# glitchprog1b-update.net
KiCad netlist of a schematic drawn in EAGLE
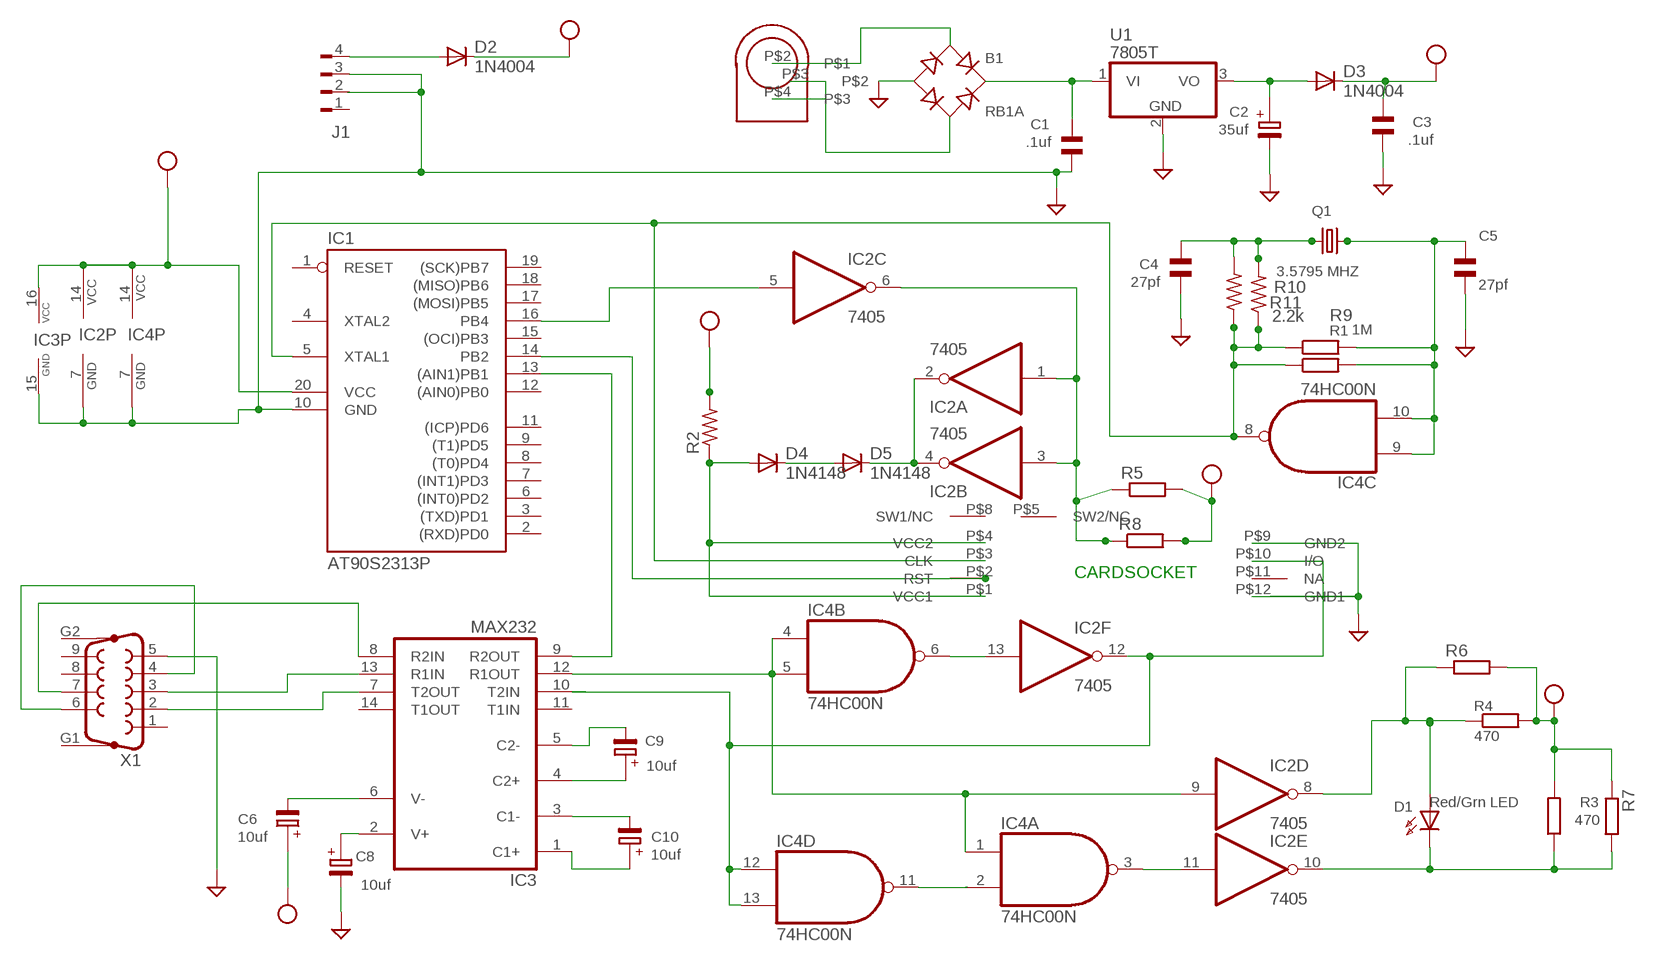
[diagram p0: schematic, sheet 1]

(export (version "E")
  (design (tool "Eeschema 10.0.6"))
  (components
    (comp (ref "B1")
      (value "RB1A")
      (footprint "eagle-import:RB1A")
      (libsource (lib "eagle-import") (part "RB1A"))
    )
    (comp (ref "C1")
      (value ".1uf")
      (footprint "eagle-import:C5B3")
      (libsource (lib "eagle-import") (part "C2,5"))
    )
    (comp (ref "C2")
      (value "35uf")
      (footprint "eagle-import:E2,0-5")
      (libsource (lib "eagle-import") (part "E2,0-5"))
    )
    (comp (ref "C3")
      (value ".1uf")
      (footprint "eagle-import:C5B3")
      (libsource (lib "eagle-import") (part "C2,5"))
    )
    (comp (ref "C4")
      (value "27pf")
      (footprint "eagle-import:C5B3")
      (libsource (lib "eagle-import") (part "C2,5"))
    )
    (comp (ref "C5")
      (value "27pf")
      (footprint "eagle-import:C5B3")
      (libsource (lib "eagle-import") (part "C2,5"))
    )
    (comp (ref "C6")
      (value "10uf")
      (footprint "eagle-import:E2,0-5")
      (libsource (lib "eagle-import") (part "E2,0-5"))
    )
    (comp (ref "C8")
      (value "10uf")
      (footprint "eagle-import:E2,0-5")
      (libsource (lib "eagle-import") (part "E2,0-5"))
    )
    (comp (ref "C9")
      (value "10uf")
      (footprint "eagle-import:E2,0-5")
      (libsource (lib "eagle-import") (part "E2,0-5"))
    )
    (comp (ref "C10")
      (value "10uf")
      (footprint "eagle-import:E2,0-5")
      (libsource (lib "eagle-import") (part "E2,0-5"))
    )
    (comp (ref "CDR1")
      (value "CHEAPREADR")
      (footprint "eagle-import:CHEAPREA")
      (libsource (lib "eagle-import") (part "CHEAPREADR"))
    )
    (comp (ref "D1")
      (value "Red/Grn LED")
      (footprint "eagle-import:LED2")
      (libsource (lib "eagle-import") (part "LED2"))
    )
    (comp (ref "D2")
      (value "1N4004")
      (footprint "eagle-import:DO41-10")
      (libsource (lib "eagle-import") (part "1N4004"))
    )
    (comp (ref "D3")
      (value "1N4004")
      (footprint "eagle-import:DO41-10")
      (libsource (lib "eagle-import") (part "1N4004"))
    )
    (comp (ref "D4")
      (value "1N4148")
      (footprint "eagle-import:DO35-10")
      (libsource (lib "eagle-import") (part "1N4148"))
    )
    (comp (ref "D5")
      (value "1N4148")
      (footprint "eagle-import:DO35-10")
      (libsource (lib "eagle-import") (part "1N4148"))
    )
    (comp (ref "IC1")
      (value "AT90S2313P")
      (footprint "eagle-import:DIL20")
      (libsource (lib "eagle-import") (part "AT90S2313P"))
    )
    (comp (ref "IC2")
      (value "7405")
      (footprint "eagle-import:DIL14")
      (libsource (lib "eagle-import") (part "7405"))
    )
    (comp (ref "IC3")
      (value "MAX232")
      (footprint "eagle-import:DIL16")
      (libsource (lib "eagle-import") (part "MAX232"))
    )
    (comp (ref "IC4")
      (value "74HC00N")
      (footprint "eagle-import:DIL14")
      (libsource (lib "eagle-import") (part "7400NALS"))
    )
    (comp (ref "J1")
      (value "FLOPPY-4")
      (footprint "eagle-import:FLOPPY-4")
      (libsource (lib "eagle-import") (part "FLOPPY-4"))
    )
    (comp (ref "Q1")
      (value "3.5795 MHZ")
      (footprint "eagle-import:HC49U-V")
      (libsource (lib "eagle-import") (part "HC49U-H"))
    )
    (comp (ref "R1")
      (value "1M")
      (footprint "eagle-import:1210")
      (libsource (lib "eagle-import") (part "0204V"))
    )
    (comp (ref "R2")
      (value "R-US_0207/10")
      (footprint "eagle-import:0207_10")
      (libsource (lib "eagle-import") (part "R-US_0207/10"))
    )
    (comp (ref "R3")
      (value "470")
      (footprint "eagle-import:1210")
      (libsource (lib "eagle-import") (part "0204V"))
    )
    (comp (ref "R4")
      (value "470")
      (footprint "eagle-import:1210@2")
      (libsource (lib "eagle-import") (part "0204/5"))
    )
    (comp (ref "R5")
      (value "R-EU_R2010")
      (footprint "eagle-import:R2010")
      (libsource (lib "eagle-import") (part "R-EU_R2010"))
    )
    (comp (ref "R6")
      (value "R-EU_0204/7")
      (footprint "eagle-import:0204_7")
      (libsource (lib "eagle-import") (part "R-EU_0204/7"))
    )
    (comp (ref "R7")
      (value "R-EU_0204/7")
      (footprint "eagle-import:0204_7")
      (libsource (lib "eagle-import") (part "R-EU_0204/7"))
    )
    (comp (ref "R8")
      (value "R-EU_0204/7")
      (footprint "eagle-import:0204_7")
      (libsource (lib "eagle-import") (part "R-EU_0204/7"))
    )
    (comp (ref "R9")
      (value "R-EU_0204/7")
      (footprint "eagle-import:0204_7")
      (libsource (lib "eagle-import") (part "R-EU_0204/7"))
    )
    (comp (ref "R10")
      (value "R-US_0204/7")
      (footprint "eagle-import:0204_7")
      (libsource (lib "eagle-import") (part "R-US_0204/7"))
    )
    (comp (ref "R11")
      (value "2.2k")
      (footprint "eagle-import:M1206")
      (libsource (lib "eagle-import") (part "R-US_M1206"))
    )
    (comp (ref "U$7")
      (value "POWER1")
      (footprint "eagle-import:POWER1")
      (libsource (lib "eagle-import") (part "POWER1"))
    )
    (comp (ref "U1")
      (value "7805T")
      (footprint "eagle-import:TO220H")
      (libsource (lib "eagle-import") (part "78XXT"))
    )
    (comp (ref "X1")
      (value "F09HP")
      (footprint "eagle-import:F09HP")
      (libsource (lib "eagle-import") (part "F09HP"))
    )
  )
  (nets
    (net (code "1") (name "GND") (class "Default")
      (node (ref "B1") (pin "-") (pinfunction "-_-") (pintype "passive"))
      (node (ref "C1") (pin "1") (pinfunction "1_1") (pintype "passive"))
      (node (ref "C2") (pin "-") (pinfunction "-_-") (pintype "passive"))
      (node (ref "C3") (pin "1") (pinfunction "1_1") (pintype "passive"))
      (node (ref "C4") (pin "1") (pinfunction "1_1") (pintype "passive"))
      (node (ref "C5") (pin "1") (pinfunction "1_1") (pintype "passive"))
      (node (ref "C8") (pin "-") (pinfunction "-_-") (pintype "passive"))
      (node (ref "CDR1") (pin "P$12") (pinfunction "GND1_P$12") (pintype "power_in"))
      (node (ref "CDR1") (pin "P$9") (pinfunction "GND2_P$9") (pintype "power_in"))
      (node (ref "IC1") (pin "10") (pinfunction "GND_10") (pintype "power_in"))
      (node (ref "IC2") (pin "7") (pinfunction "GND_7") (pintype "power_in"))
      (node (ref "IC3") (pin "15") (pinfunction "GND_15") (pintype "power_in"))
      (node (ref "IC4") (pin "7") (pinfunction "GND_7") (pintype "power_in"))
      (node (ref "J1") (pin "3") (pinfunction "3_3") (pintype "passive"))
      (node (ref "U1") (pin "2") (pinfunction "GND_2") (pintype "passive"))
      (node (ref "X1") (pin "5") (pinfunction "5_5") (pintype "passive"))
    )
    (net (code "2") (name "Net-(C4-Pad2)") (class "Default")
      (node (ref "C4") (pin "2") (pinfunction "2_2") (pintype "passive"))
      (node (ref "Q1") (pin "1") (pinfunction "1_1") (pintype "passive"))
      (node (ref "R10") (pin "2") (pinfunction "2_2") (pintype "passive"))
      (node (ref "R11") (pin "2") (pinfunction "2_2") (pintype "passive"))
    )
    (net (code "3") (name "Net-(CDR1-CLK)") (class "Default")
      (node (ref "CDR1") (pin "P$3") (pinfunction "CLK_P$3") (pintype "input"))
      (node (ref "IC1") (pin "5") (pinfunction "XTAL1_5") (pintype "bidirectional"))
      (node (ref "IC4") (pin "8") (pinfunction "O_8") (pintype "output"))
      (node (ref "R1") (pin "1") (pinfunction "1_1") (pintype "passive"))
      (node (ref "R10") (pin "1") (pinfunction "1_1") (pintype "passive"))
      (node (ref "R11") (pin "1") (pinfunction "1_1") (pintype "passive"))
      (node (ref "R9") (pin "1") (pinfunction "1_1") (pintype "passive"))
    )
    (net (code "4") (name "Net-(CDR1-I{slash}O)") (class "Default")
      (node (ref "CDR1") (pin "P$10") (pinfunction "I/O_P$10") (pintype "bidirectional"))
      (node (ref "IC2") (pin "12") (pinfunction "O_12") (pintype "open_collector"))
      (node (ref "IC3") (pin "10") (pinfunction "T2IN_10") (pintype "input"))
      (node (ref "IC4") (pin "12") (pinfunction "I0_12") (pintype "input"))
      (node (ref "IC4") (pin "13") (pinfunction "I1_13") (pintype "input"))
    )
    (net (code "5") (name "Net-(CDR1-RST)") (class "Default")
      (node (ref "CDR1") (pin "P$2") (pinfunction "RST_P$2") (pintype "input"))
      (node (ref "IC1") (pin "14") (pinfunction "PB2_14") (pintype "bidirectional"))
    )
    (net (code "6") (name "Net-(CDR1-VCC1)") (class "Default")
      (node (ref "CDR1") (pin "P$1") (pinfunction "VCC1_P$1") (pintype "power_in"))
      (node (ref "CDR1") (pin "P$4") (pinfunction "VCC2_P$4") (pintype "power_in"))
      (node (ref "D4") (pin "A") (pinfunction "A_A") (pintype "passive"))
      (node (ref "R2") (pin "1") (pinfunction "1_1") (pintype "passive"))
    )
    (net (code "7") (name "Net-(D2-PadA)") (class "Default")
      (node (ref "D2") (pin "A") (pinfunction "A_A") (pintype "passive"))
      (node (ref "J1") (pin "4") (pinfunction "4_4") (pintype "passive"))
    )
    (net (code "8") (name "Net-(D4-C)") (class "Default")
      (node (ref "D4") (pin "K") (pinfunction "C_K") (pintype "passive"))
      (node (ref "D5") (pin "A") (pinfunction "A_A") (pintype "passive"))
    )
    (net (code "9") (name "Net-(D5-C)") (class "Default")
      (node (ref "D5") (pin "K") (pinfunction "C_K") (pintype "passive"))
      (node (ref "IC2") (pin "2") (pinfunction "O_2") (pintype "open_collector"))
      (node (ref "IC2") (pin "4") (pinfunction "O_4") (pintype "open_collector"))
    )
    (net (code "10") (name "Net-(IC1-(AIN1)PB1)") (class "Default")
      (node (ref "IC1") (pin "13") (pinfunction "(AIN1)PB1_13") (pintype "bidirectional"))
      (node (ref "IC3") (pin "9") (pinfunction "R2OUT_9") (pintype "output"))
    )
    (net (code "11") (name "Net-(IC1-PB4)") (class "Default")
      (node (ref "IC1") (pin "16") (pinfunction "PB4_16") (pintype "bidirectional"))
      (node (ref "IC2") (pin "5") (pinfunction "I_5") (pintype "input"))
    )
    (net (code "12") (name "Net-(IC2A-I)") (class "Default")
      (node (ref "IC2") (pin "1") (pinfunction "I_1") (pintype "input"))
      (node (ref "IC2") (pin "3") (pinfunction "I_3") (pintype "input"))
      (node (ref "IC2") (pin "6") (pinfunction "O_6") (pintype "open_collector"))
      (node (ref "R5") (pin "1") (pinfunction "1_1") (pintype "passive"))
      (node (ref "R8") (pin "1") (pinfunction "1_1") (pintype "passive"))
    )
    (net (code "13") (name "Net-(IC2D-I)") (class "Default")
      (node (ref "IC2") (pin "9") (pinfunction "I_9") (pintype "input"))
      (node (ref "IC3") (pin "12") (pinfunction "R1OUT_12") (pintype "output"))
      (node (ref "IC4") (pin "1") (pinfunction "I0_1") (pintype "input"))
      (node (ref "IC4") (pin "4") (pinfunction "I0_4") (pintype "input"))
      (node (ref "IC4") (pin "5") (pinfunction "I1_5") (pintype "input"))
    )
    (net (code "14") (name "Net-(IC2D-O)") (class "Default")
      (node (ref "D1") (pin "A") (pinfunction "A_A") (pintype "passive"))
      (node (ref "IC2") (pin "8") (pinfunction "O_8") (pintype "open_collector"))
      (node (ref "R4") (pin "1") (pinfunction "1_1") (pintype "passive"))
      (node (ref "R6") (pin "1") (pinfunction "1_1") (pintype "passive"))
    )
    (net (code "15") (name "Net-(IC2E-I)") (class "Default")
      (node (ref "IC2") (pin "11") (pinfunction "I_11") (pintype "input"))
      (node (ref "IC4") (pin "3") (pinfunction "O_3") (pintype "output"))
    )
    (net (code "16") (name "Net-(IC2E-O)") (class "Default")
      (node (ref "D1") (pin "K") (pinfunction "K_K") (pintype "passive"))
      (node (ref "IC2") (pin "10") (pinfunction "O_10") (pintype "open_collector"))
      (node (ref "R3") (pin "1") (pinfunction "1_1") (pintype "passive"))
      (node (ref "R7") (pin "2") (pinfunction "2_2") (pintype "passive"))
    )
    (net (code "17") (name "Net-(IC2F-I)") (class "Default")
      (node (ref "IC2") (pin "13") (pinfunction "I_13") (pintype "input"))
      (node (ref "IC4") (pin "6") (pinfunction "O_6") (pintype "output"))
    )
    (net (code "18") (name "Net-(IC3A-C1+)") (class "Default")
      (node (ref "C10") (pin "+") (pinfunction "+_+") (pintype "passive"))
      (node (ref "IC3") (pin "1") (pinfunction "C1+_1") (pintype "bidirectional"))
    )
    (net (code "19") (name "Net-(IC3A-C1-)") (class "Default")
      (node (ref "C10") (pin "-") (pinfunction "-_-") (pintype "passive"))
      (node (ref "IC3") (pin "3") (pinfunction "C1-_3") (pintype "bidirectional"))
    )
    (net (code "20") (name "Net-(IC3A-C2+)") (class "Default")
      (node (ref "C9") (pin "+") (pinfunction "+_+") (pintype "passive"))
      (node (ref "IC3") (pin "4") (pinfunction "C2+_4") (pintype "bidirectional"))
    )
    (net (code "21") (name "Net-(IC3A-C2-)") (class "Default")
      (node (ref "C9") (pin "-") (pinfunction "-_-") (pintype "passive"))
      (node (ref "IC3") (pin "5") (pinfunction "C2-_5") (pintype "bidirectional"))
    )
    (net (code "22") (name "Net-(IC3A-R1IN)") (class "Default")
      (node (ref "IC3") (pin "13") (pinfunction "R1IN_13") (pintype "input"))
      (node (ref "X1") (pin "3") (pinfunction "3_3") (pintype "passive"))
    )
    (net (code "23") (name "Net-(IC3A-R2IN)") (class "Default")
      (node (ref "IC3") (pin "8") (pinfunction "R2IN_8") (pintype "input"))
      (node (ref "X1") (pin "7") (pinfunction "7_7") (pintype "passive"))
    )
    (net (code "24") (name "Net-(IC3A-T2OUT)") (class "Default")
      (node (ref "IC3") (pin "7") (pinfunction "T2OUT_7") (pintype "output"))
      (node (ref "X1") (pin "2") (pinfunction "2_2") (pintype "passive"))
    )
    (net (code "25") (name "Net-(IC3A-V+)") (class "Default")
      (node (ref "C8") (pin "+") (pinfunction "+_+") (pintype "passive"))
      (node (ref "IC3") (pin "2") (pinfunction "V+_2") (pintype "bidirectional"))
    )
    (net (code "26") (name "Net-(IC3A-V-)") (class "Default")
      (node (ref "C6") (pin "-") (pinfunction "-_-") (pintype "passive"))
      (node (ref "IC3") (pin "6") (pinfunction "V-_6") (pintype "bidirectional"))
    )
    (net (code "27") (name "Net-(IC4A-I1)") (class "Default")
      (node (ref "IC4") (pin "11") (pinfunction "O_11") (pintype "output"))
      (node (ref "IC4") (pin "2") (pinfunction "I1_2") (pintype "input"))
    )
    (net (code "28") (name "Net-(IC4C-I0)") (class "Default")
      (node (ref "C5") (pin "2") (pinfunction "2_2") (pintype "passive"))
      (node (ref "IC4") (pin "10") (pinfunction "I1_10") (pintype "input"))
      (node (ref "IC4") (pin "9") (pinfunction "I0_9") (pintype "input"))
      (node (ref "Q1") (pin "2") (pinfunction "2_2") (pintype "passive"))
      (node (ref "R1") (pin "2") (pinfunction "2_2") (pintype "passive"))
      (node (ref "R9") (pin "2") (pinfunction "2_2") (pintype "passive"))
    )
    (net (code "29") (name "Net-(U$7-P$1)") (class "Default")
      (node (ref "B1") (pin "AC1") (pinfunction "AC1_AC1") (pintype "passive"))
      (node (ref "U$7") (pin "P$2") (pinfunction "P$1_P$2") (pintype "bidirectional"))
    )
    (net (code "30") (name "Net-(U$7-P$2)") (class "Default")
      (node (ref "B1") (pin "AC2") (pinfunction "AC2_AC2") (pintype "passive"))
      (node (ref "U$7") (pin "P$3") (pinfunction "P$2_P$3") (pintype "bidirectional"))
      (node (ref "U$7") (pin "P$4") (pinfunction "P$3_P$4") (pintype "bidirectional"))
    )
    (net (code "31") (name "Net-(U1-VI)") (class "Default")
      (node (ref "B1") (pin "+") (pinfunction "+_+") (pintype "passive"))
      (node (ref "C1") (pin "2") (pinfunction "2_2") (pintype "passive"))
      (node (ref "U1") (pin "1") (pinfunction "VI_1") (pintype "input"))
    )
    (net (code "32") (name "Net-(U1-VO)") (class "Default")
      (node (ref "C2") (pin "+") (pinfunction "+_+") (pintype "passive"))
      (node (ref "D3") (pin "A") (pinfunction "A_A") (pintype "passive"))
      (node (ref "U1") (pin "3") (pinfunction "VO_3") (pintype "output"))
    )
    (net (code "33") (name "Net-(X1-Pad4)") (class "Default")
      (node (ref "X1") (pin "4") (pinfunction "4_4") (pintype "passive"))
      (node (ref "X1") (pin "6") (pinfunction "6_6") (pintype "passive"))
    )
    (net (code "34") (name "VCC") (class "Default")
      (node (ref "C3") (pin "2") (pinfunction "2_2") (pintype "passive"))
      (node (ref "C6") (pin "+") (pinfunction "+_+") (pintype "passive"))
      (node (ref "D2") (pin "K") (pinfunction "C_K") (pintype "passive"))
      (node (ref "D3") (pin "K") (pinfunction "C_K") (pintype "passive"))
      (node (ref "IC1") (pin "20") (pinfunction "VCC_20") (pintype "power_in"))
      (node (ref "IC2") (pin "14") (pinfunction "VCC_14") (pintype "power_in"))
      (node (ref "IC3") (pin "16") (pinfunction "VCC_16") (pintype "power_in"))
      (node (ref "IC4") (pin "14") (pinfunction "VCC_14") (pintype "power_in"))
      (node (ref "R2") (pin "2") (pinfunction "2_2") (pintype "passive"))
      (node (ref "R3") (pin "2") (pinfunction "2_2") (pintype "passive"))
      (node (ref "R4") (pin "2") (pinfunction "2_2") (pintype "passive"))
      (node (ref "R5") (pin "2") (pinfunction "2_2") (pintype "passive"))
      (node (ref "R6") (pin "2") (pinfunction "2_2") (pintype "passive"))
      (node (ref "R7") (pin "1") (pinfunction "1_1") (pintype "passive"))
      (node (ref "R8") (pin "2") (pinfunction "2_2") (pintype "passive"))
    )
    (net (code "35") (name "unconnected-(CDR1-NA-PadP$11)") (class "Default")
      (node (ref "CDR1") (pin "P$11") (pinfunction "NA_P$11") (pintype "no_connect"))
    )
    (net (code "36") (name "unconnected-(CDR1-SW1{slash}NC-PadP$8)") (class "Default")
      (node (ref "CDR1") (pin "P$8") (pinfunction "SW1/NC_P$8") (pintype "bidirectional"))
    )
    (net (code "37") (name "unconnected-(CDR1-SW2{slash}NC-PadP$5)") (class "Default")
      (node (ref "CDR1") (pin "P$5") (pinfunction "SW2/NC_P$5") (pintype "bidirectional"))
    )
    (net (code "38") (name "unconnected-(IC1-(AIN0)PB0-Pad12)") (class "Default")
      (node (ref "IC1") (pin "12") (pinfunction "(AIN0)PB0_12") (pintype "bidirectional"))
    )
    (net (code "39") (name "unconnected-(IC1-(ICP)PD6-Pad11)") (class "Default")
      (node (ref "IC1") (pin "11") (pinfunction "(ICP)PD6_11") (pintype "bidirectional"))
    )
    (net (code "40") (name "unconnected-(IC1-(INT0)PD2-Pad6)") (class "Default")
      (node (ref "IC1") (pin "6") (pinfunction "(INT0)PD2_6") (pintype "bidirectional"))
    )
    (net (code "41") (name "unconnected-(IC1-(INT1)PD3-Pad7)") (class "Default")
      (node (ref "IC1") (pin "7") (pinfunction "(INT1)PD3_7") (pintype "bidirectional"))
    )
    (net (code "42") (name "unconnected-(IC1-(MISO)PB6-Pad18)") (class "Default")
      (node (ref "IC1") (pin "18") (pinfunction "(MISO)PB6_18") (pintype "bidirectional"))
    )
    (net (code "43") (name "unconnected-(IC1-(MOSI)PB5-Pad17)") (class "Default")
      (node (ref "IC1") (pin "17") (pinfunction "(MOSI)PB5_17") (pintype "bidirectional"))
    )
    (net (code "44") (name "unconnected-(IC1-(OCI)PB3-Pad15)") (class "Default")
      (node (ref "IC1") (pin "15") (pinfunction "(OCI)PB3_15") (pintype "bidirectional"))
    )
    (net (code "45") (name "unconnected-(IC1-(RXD)PD0-Pad2)") (class "Default")
      (node (ref "IC1") (pin "2") (pinfunction "(RXD)PD0_2") (pintype "bidirectional"))
    )
    (net (code "46") (name "unconnected-(IC1-(SCK)PB7-Pad19)") (class "Default")
      (node (ref "IC1") (pin "19") (pinfunction "(SCK)PB7_19") (pintype "bidirectional"))
    )
    (net (code "47") (name "unconnected-(IC1-(T0)PD4-Pad8)") (class "Default")
      (node (ref "IC1") (pin "8") (pinfunction "(T0)PD4_8") (pintype "bidirectional"))
    )
    (net (code "48") (name "unconnected-(IC1-(T1)PD5-Pad9)") (class "Default")
      (node (ref "IC1") (pin "9") (pinfunction "(T1)PD5_9") (pintype "bidirectional"))
    )
    (net (code "49") (name "unconnected-(IC1-(TXD)PD1-Pad3)") (class "Default")
      (node (ref "IC1") (pin "3") (pinfunction "(TXD)PD1_3") (pintype "bidirectional"))
    )
    (net (code "50") (name "unconnected-(IC1-RESET-Pad1)") (class "Default")
      (node (ref "IC1") (pin "1") (pinfunction "RESET_1") (pintype "bidirectional"))
    )
    (net (code "51") (name "unconnected-(IC1-XTAL2-Pad4)") (class "Default")
      (node (ref "IC1") (pin "4") (pinfunction "XTAL2_4") (pintype "bidirectional"))
    )
    (net (code "52") (name "unconnected-(IC3A-T1IN-Pad11)") (class "Default")
      (node (ref "IC3") (pin "11") (pinfunction "T1IN_11") (pintype "input"))
    )
    (net (code "53") (name "unconnected-(IC3A-T1OUT-Pad14)") (class "Default")
      (node (ref "IC3") (pin "14") (pinfunction "T1OUT_14") (pintype "output"))
    )
    (net (code "54") (name "unconnected-(J1-Pad1)") (class "Default")
      (node (ref "J1") (pin "1") (pinfunction "1_1") (pintype "passive"))
    )
    (net (code "55") (name "unconnected-(J1-Pad2)") (class "Default")
      (node (ref "J1") (pin "2") (pinfunction "2_2") (pintype "passive"))
    )
    (net (code "56") (name "unconnected-(X1-Pad1)") (class "Default")
      (node (ref "X1") (pin "1") (pinfunction "1_1") (pintype "passive"))
    )
    (net (code "57") (name "unconnected-(X1-Pad8)") (class "Default")
      (node (ref "X1") (pin "8") (pinfunction "8_8") (pintype "passive"))
    )
    (net (code "58") (name "unconnected-(X1-Pad9)") (class "Default")
      (node (ref "X1") (pin "9") (pinfunction "9_9") (pintype "passive"))
    )
    (net (code "59") (name "unconnected-(X1-PadG1)") (class "Default")
      (node (ref "X1") (pin "G1") (pinfunction "G1_G1") (pintype "passive"))
    )
    (net (code "60") (name "unconnected-(X1-PadG2)") (class "Default")
      (node (ref "X1") (pin "G2") (pinfunction "G2_G2") (pintype "passive"))
    )
  )
)
